# SparkFun_ESP8266_Thing_dimensions_added.net
KiCad netlist of a schematic drawn in EAGLE
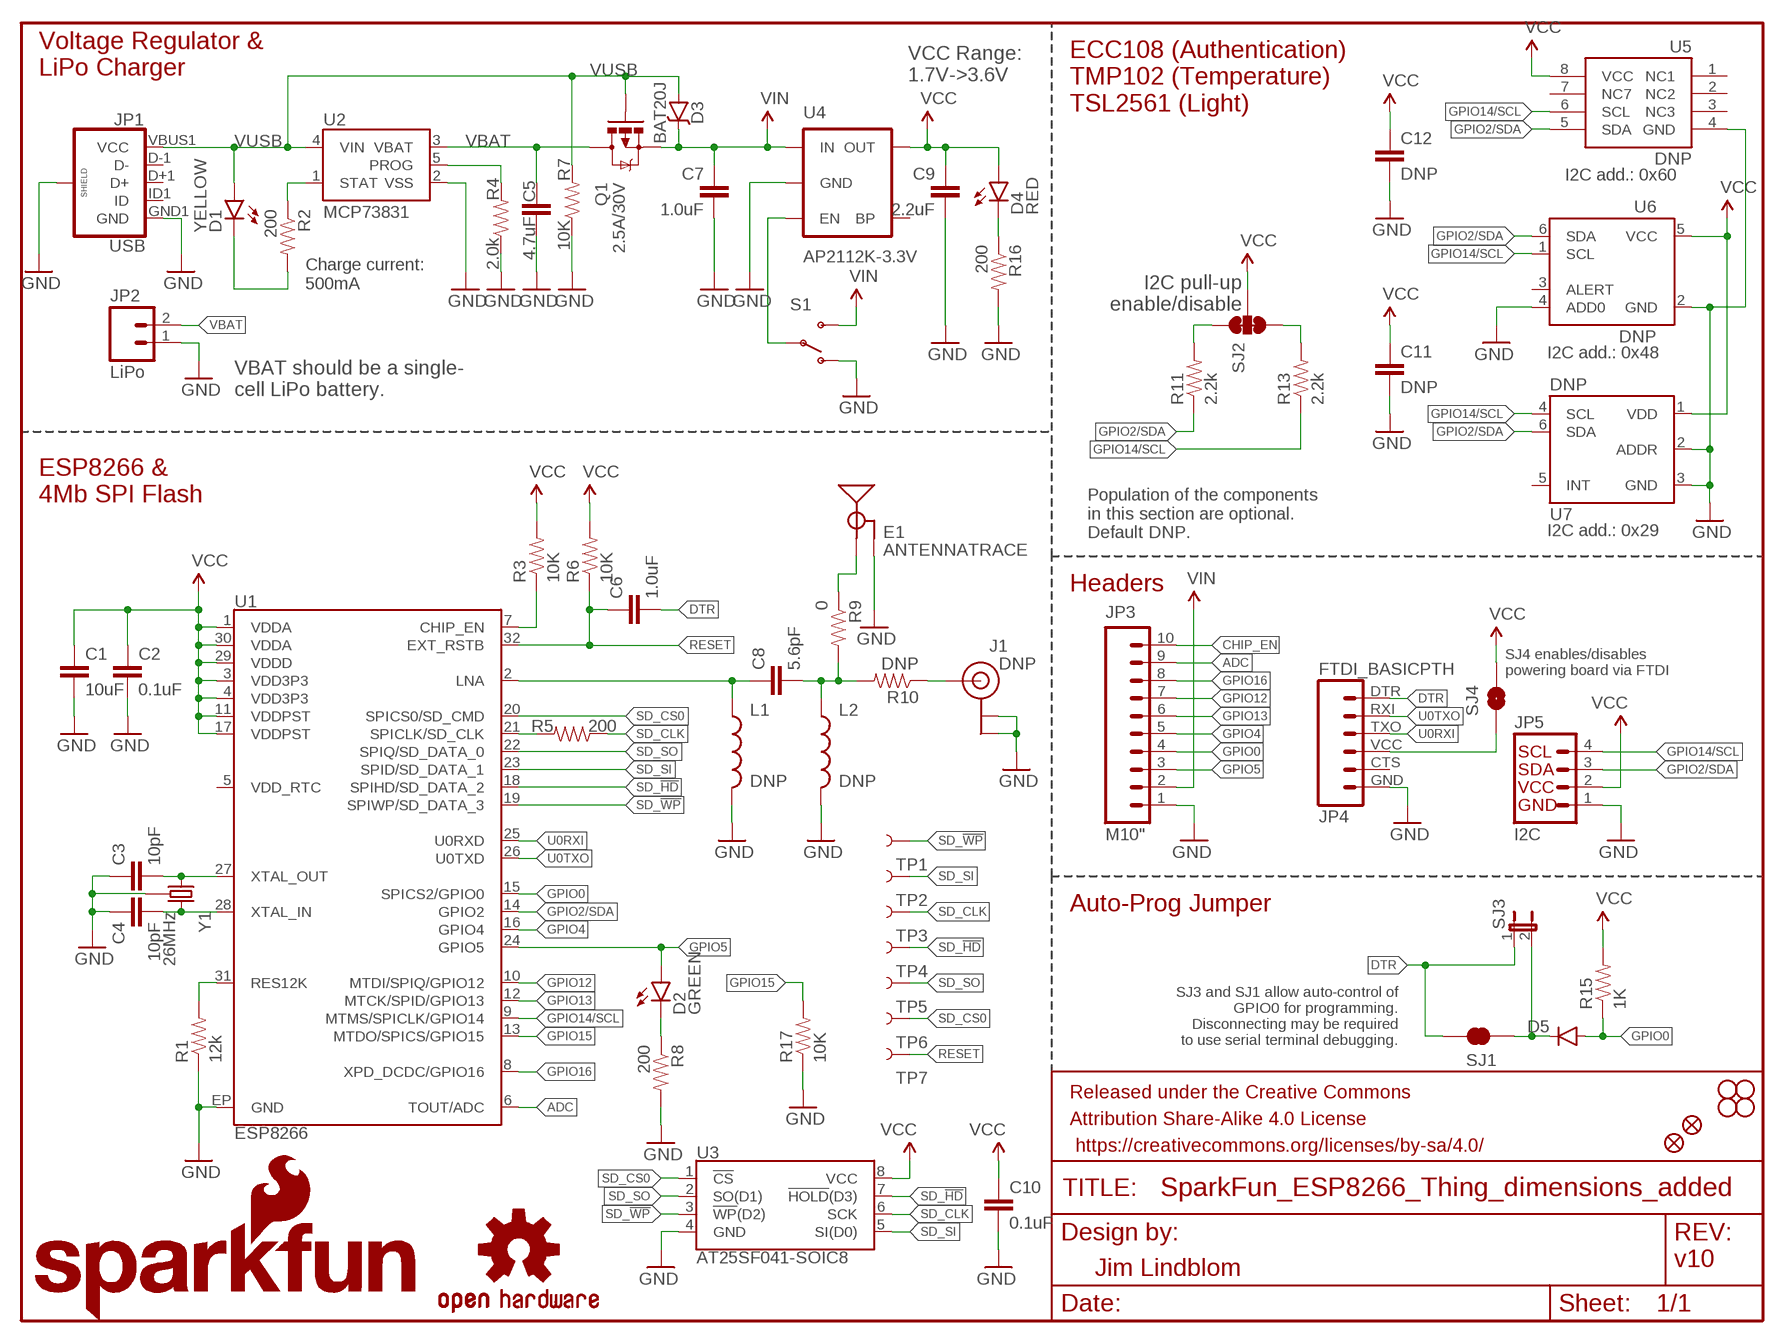
[diagram p0: schematic, sheet 1]

(export (version "E")
  (design (tool "Eeschema 10.0.6"))
  (components
    (comp (ref "C1")
      (value "10uF")
      (footprint "eagle-import:0603-CAP")
      (libsource (lib "eagle-import") (part "10UF-6.3V-20%(0603)"))
    )
    (comp (ref "C2")
      (value "0.1uF")
      (footprint "eagle-import:0603-CAP")
      (libsource (lib "eagle-import") (part "0.1UF-25V(+80/-20%)(0603)"))
    )
    (comp (ref "C3")
      (value "10pF")
      (footprint "eagle-import:0603-CAP")
      (libsource (lib "eagle-import") (part "10PF-50V-5%(0603)"))
    )
    (comp (ref "C4")
      (value "10pF")
      (footprint "eagle-import:0603-CAP")
      (libsource (lib "eagle-import") (part "10PF-50V-5%(0603)"))
    )
    (comp (ref "C5")
      (value "4.7uF")
      (footprint "eagle-import:0603-CAP")
      (libsource (lib "eagle-import") (part "4.7UF-6.3V-10%(0603)0603"))
    )
    (comp (ref "C6")
      (value "1.0uF")
      (footprint "eagle-import:0603-CAP")
      (libsource (lib "eagle-import") (part "1.0UF-16V-10%(0603)"))
    )
    (comp (ref "C7")
      (value "1.0uF")
      (footprint "eagle-import:0805")
      (libsource (lib "eagle-import") (part "1.0UF-25V-+80/-20(0805)"))
    )
    (comp (ref "C8")
      (value "5.6pF")
      (footprint "eagle-import:0603-CAP")
      (libsource (lib "eagle-import") (part "CAP0603-CAP"))
    )
    (comp (ref "C9")
      (value "2.2uF")
      (footprint "eagle-import:0603-CAP")
      (libsource (lib "eagle-import") (part "2.2UF-10V-20%(0603)"))
    )
    (comp (ref "C10")
      (value "0.1uF")
      (footprint "eagle-import:0603-CAP")
      (libsource (lib "eagle-import") (part "0.1UF-25V(+80/-20%)(0603)"))
    )
    (comp (ref "C11")
      (value "DNP")
      (footprint "eagle-import:0603-CAP")
      (libsource (lib "eagle-import") (part "0.1UF-25V(+80/-20%)(0603)"))
    )
    (comp (ref "C12")
      (value "DNP")
      (footprint "eagle-import:0603-CAP")
      (libsource (lib "eagle-import") (part "0.1UF-25V(+80/-20%)(0603)"))
    )
    (comp (ref "D1")
      (value "YELLOW")
      (footprint "eagle-import:LED-0603")
      (libsource (lib "eagle-import") (part "LED-YELLOW0603"))
    )
    (comp (ref "D2")
      (value "GREEN")
      (footprint "eagle-import:LED-0603")
      (libsource (lib "eagle-import") (part "LED-GREEN0603"))
    )
    (comp (ref "D3")
      (value "BAT20J")
      (footprint "eagle-import:SOD-323")
      (libsource (lib "eagle-import") (part "DIODE-SCHOTTKY-BAT20J"))
    )
    (comp (ref "D4")
      (value "RED")
      (footprint "eagle-import:LED-0603")
      (libsource (lib "eagle-import") (part "LED-RED0603"))
    )
    (comp (ref "D5")
      (value "DIODEBAS16")
      (footprint "eagle-import:SOD-323")
      (libsource (lib "eagle-import") (part "DIODEBAS16"))
    )
    (comp (ref "E1")
      (value "ANTENNATRACE")
      (footprint "eagle-import:TRACE_ANTENNA_2.4GHZ_25.7MM")
      (libsource (lib "eagle-import") (part "ANTENNATRACE"))
    )
    (comp (ref "FID1")
      (value "FIDUCIAL1X2")
      (footprint "eagle-import:FIDUCIAL-1X2")
      (libsource (lib "eagle-import") (part "FIDUCIAL1X2"))
    )
    (comp (ref "FID2")
      (value "FIDUCIAL1X2")
      (footprint "eagle-import:FIDUCIAL-1X2")
      (libsource (lib "eagle-import") (part "FIDUCIAL1X2"))
    )
    (comp (ref "FRAME1")
      (value "FRAME-LETTER")
      (footprint "eagle-import:CREATIVE_COMMONS")
      (libsource (lib "eagle-import") (part "FRAME-LETTER"))
    )
    (comp (ref "J1")
      (value "DNP")
      (footprint "eagle-import:U.FL")
      (libsource (lib "eagle-import") (part "U.FL"))
    )
    (comp (ref "JP1")
      (value "USB")
      (footprint "eagle-import:USB-B-MICRO-SMD_V03")
      (libsource (lib "eagle-import") (part "USB_MICROB_PLUGCONN-11752"))
    )
    (comp (ref "JP2")
      (value "LiPo")
      (footprint "eagle-import:JST-2-PTH")
      (libsource (lib "eagle-import") (part "M02JST-PTH-2"))
    )
    (comp (ref "JP3")
      (value "M10\"")
      (footprint "eagle-import:1X10")
      (libsource (lib "eagle-import") (part "M10{dblquote}"))
    )
    (comp (ref "JP4")
      (value "FTDI_BASICPTH")
      (footprint "eagle-import:FTDI_BASIC")
      (libsource (lib "eagle-import") (part "FTDI_BASICPTH"))
    )
    (comp (ref "JP5")
      (value "I2C")
      (footprint "eagle-import:1X04")
      (libsource (lib "eagle-import") (part "I2C_STANDARD"))
    )
    (comp (ref "L1")
      (value "DNP")
      (footprint "eagle-import:0603")
      (libsource (lib "eagle-import") (part "INDUCTOR0603"))
    )
    (comp (ref "L2")
      (value "DNP")
      (footprint "eagle-import:0603")
      (libsource (lib "eagle-import") (part "INDUCTOR0603"))
    )
    (comp (ref "LOGO1")
      (value "SFE_LOGO_NAME.2_INCH")
      (footprint "eagle-import:SFE_LOGO_NAME_.2")
      (libsource (lib "eagle-import") (part "SFE_LOGO_NAME.2_INCH"))
    )
    (comp (ref "LOGO3")
      (value "SFE_LOGO_FLAME.1_INCH")
      (footprint "eagle-import:SFE_LOGO_FLAME_.1")
      (libsource (lib "eagle-import") (part "SFE_LOGO_FLAME.1_INCH"))
    )
    (comp (ref "LOGO4")
      (value "OSHW-LOGOS")
      (footprint "eagle-import:OSHW-LOGO-S")
      (libsource (lib "eagle-import") (part "OSHW-LOGOS"))
    )
    (comp (ref "Q1")
      (value "2.5A/30V")
      (footprint "eagle-import:SOT23-3")
      (libsource (lib "eagle-import") (part "MOSFET-PCHANNELDMG2307L"))
    )
    (comp (ref "R1")
      (value "12k")
      (footprint "eagle-import:0603-RES")
      (libsource (lib "eagle-import") (part "12KOHM-1/10W-1%(0603)"))
    )
    (comp (ref "R2")
      (value "200")
      (footprint "eagle-import:0603-RES")
      (libsource (lib "eagle-import") (part "200OHM1/10W1%(0603)"))
    )
    (comp (ref "R3")
      (value "10K")
      (footprint "eagle-import:0603-RES")
      (libsource (lib "eagle-import") (part "10KOHM1/10W1%(0603)0603"))
    )
    (comp (ref "R4")
      (value "2.0k")
      (footprint "eagle-import:0603-RES")
      (libsource (lib "eagle-import") (part "2.0KOHM1/10W5%(0603)"))
    )
    (comp (ref "R5")
      (value "200")
      (footprint "eagle-import:0603-RES")
      (libsource (lib "eagle-import") (part "200OHM1/10W1%(0603)"))
    )
    (comp (ref "R6")
      (value "10K")
      (footprint "eagle-import:0603-RES")
      (libsource (lib "eagle-import") (part "10KOHM1/10W1%(0603)0603"))
    )
    (comp (ref "R7")
      (value "10K")
      (footprint "eagle-import:0603-RES")
      (libsource (lib "eagle-import") (part "10KOHM1/10W1%(0603)0603"))
    )
    (comp (ref "R8")
      (value "200")
      (footprint "eagle-import:0603-RES")
      (libsource (lib "eagle-import") (part "200OHM1/10W1%(0603)"))
    )
    (comp (ref "R9")
      (value "0")
      (footprint "eagle-import:0603")
      (libsource (lib "eagle-import") (part "0OHM1/10W5%(0603)"))
    )
    (comp (ref "R10")
      (value "DNP")
      (footprint "eagle-import:0603-RES")
      (libsource (lib "eagle-import") (part "RESISTOR0603-RES"))
    )
    (comp (ref "R11")
      (value "2.2k")
      (footprint "eagle-import:0603-RES")
      (libsource (lib "eagle-import") (part "2.2KOHM1/10W1%(0603)"))
    )
    (comp (ref "R13")
      (value "2.2k")
      (footprint "eagle-import:0603-RES")
      (libsource (lib "eagle-import") (part "2.2KOHM1/10W1%(0603)"))
    )
    (comp (ref "R15")
      (value "1K")
      (footprint "eagle-import:0603-RES")
      (libsource (lib "eagle-import") (part "1KOHM1/10W1%(0603)"))
    )
    (comp (ref "R16")
      (value "200")
      (footprint "eagle-import:0603-RES")
      (libsource (lib "eagle-import") (part "200OHM1/10W1%(0603)"))
    )
    (comp (ref "R17")
      (value "10K")
      (footprint "eagle-import:0603-RES")
      (libsource (lib "eagle-import") (part "10KOHM1/10W1%(0603)0603"))
    )
    (comp (ref "S1")
      (value "SWITCH-SPDT-SMD-A")
      (footprint "eagle-import:SWITCH-SPST-SMD-A")
      (libsource (lib "eagle-import") (part "SWITCH-SPDT-SMD-A"))
    )
    (comp (ref "SJ1")
      (value "JUMPER-PAD-2-NC_BY_TRACE")
      (footprint "eagle-import:PAD-JUMPER-2-NC_BY_TRACE_YES_SILK")
      (libsource (lib "eagle-import") (part "JUMPER-PAD-2-NC_BY_TRACE"))
    )
    (comp (ref "SJ2")
      (value "JUMPER-PAD-3-NC_BY_TRACE")
      (footprint "eagle-import:PAD-JUMPER-3-3OF3_NC_BY_TRACE_YES_SILK_FULL_BOX")
      (libsource (lib "eagle-import") (part "JUMPER-PAD-3-NC_BY_TRACE"))
    )
    (comp (ref "SJ3")
      (value "JUMPER-PTH-2-NC")
      (footprint "eagle-import:PTH-JUMPER-NC_BOTTOM_NO_SILK")
      (libsource (lib "eagle-import") (part "JUMPER-PTH-2-NC"))
    )
    (comp (ref "SJ4")
      (value "JUMPER-PAD-2-NOYES_SILK")
      (footprint "eagle-import:PAD-JUMPER-2-NO_YES_SILK")
      (libsource (lib "eagle-import") (part "JUMPER-PAD-2-NOYES_SILK"))
    )
    (comp (ref "STANDOFF1")
      (value "STAND-OFF")
      (footprint "eagle-import:STAND-OFF")
      (libsource (lib "eagle-import") (part "STAND-OFF"))
    )
    (comp (ref "STANDOFF2")
      (value "STAND-OFF")
      (footprint "eagle-import:STAND-OFF")
      (libsource (lib "eagle-import") (part "STAND-OFF"))
    )
    (comp (ref "STANDOFF3")
      (value "STAND-OFF")
      (footprint "eagle-import:STAND-OFF")
      (libsource (lib "eagle-import") (part "STAND-OFF"))
    )
    (comp (ref "STANDOFF4")
      (value "STAND-OFF")
      (footprint "eagle-import:STAND-OFF")
      (libsource (lib "eagle-import") (part "STAND-OFF"))
    )
    (comp (ref "TP1")
      (value "TEST-POINT3X5")
      (footprint "eagle-import:PAD.03X.05")
      (libsource (lib "eagle-import") (part "TEST-POINT3X5"))
    )
    (comp (ref "TP2")
      (value "TEST-POINT3X5")
      (footprint "eagle-import:PAD.03X.05")
      (libsource (lib "eagle-import") (part "TEST-POINT3X5"))
    )
    (comp (ref "TP3")
      (value "TEST-POINT3X5")
      (footprint "eagle-import:PAD.03X.05")
      (libsource (lib "eagle-import") (part "TEST-POINT3X5"))
    )
    (comp (ref "TP4")
      (value "TEST-POINT3X5")
      (footprint "eagle-import:PAD.03X.05")
      (libsource (lib "eagle-import") (part "TEST-POINT3X5"))
    )
    (comp (ref "TP5")
      (value "TEST-POINT3X5")
      (footprint "eagle-import:PAD.03X.05")
      (libsource (lib "eagle-import") (part "TEST-POINT3X5"))
    )
    (comp (ref "TP6")
      (value "TEST-POINT3X5")
      (footprint "eagle-import:PAD.03X.05")
      (libsource (lib "eagle-import") (part "TEST-POINT3X5"))
    )
    (comp (ref "TP7")
      (value "TEST-POINT3X5")
      (footprint "eagle-import:PAD.03X.05")
      (libsource (lib "eagle-import") (part "TEST-POINT3X5"))
    )
    (comp (ref "U1")
      (value "ESP8266")
      (footprint "eagle-import:QFN32")
      (libsource (lib "eagle-import") (part "ESP8266"))
    )
    (comp (ref "U2")
      (value "MCP73831")
      (footprint "eagle-import:SOT23-5")
      (libsource (lib "eagle-import") (part "MCP73831"))
    )
    (comp (ref "U3")
      (value "AT25SF041-SOIC8")
      (footprint "eagle-import:SO08")
      (libsource (lib "eagle-import") (part "AT25SF041-SOIC8"))
    )
    (comp (ref "U4")
      (value "AP2112K-3.3V")
      (footprint "eagle-import:SOT23-5")
      (libsource (lib "eagle-import") (part "V_REG_LDOSMD"))
    )
    (comp (ref "U5")
      (value "DNP")
      (footprint "eagle-import:UDFN8")
      (libsource (lib "eagle-import") (part "ATECC108-MAHDA"))
    )
    (comp (ref "U6")
      (value "DNP")
      (footprint "eagle-import:SOT563-2")
      (libsource (lib "eagle-import") (part "TMP1021{colon}1"))
    )
    (comp (ref "U7")
      (value "DNP")
      (footprint "eagle-import:FN-6")
      (libsource (lib "eagle-import") (part "TSL2561FN"))
    )
    (comp (ref "Y1")
      (value "26MHz")
      (footprint "eagle-import:CRYSTAL-SMD-3.2X2.5")
      (libsource (lib "eagle-import") (part "CRYSTAL-GROUNDED3.2X2.5"))
    )
  )
  (nets
    (net (code "1") (name "/SD_~{HD}") (class "Default")
      (node (ref "TP4") (pin "P$1") (pinfunction "1_P$1") (pintype "bidirectional"))
      (node (ref "U1") (pin "18") (pinfunction "SPIHD/SD_DATA_2_18") (pintype "bidirectional"))
      (node (ref "U3") (pin "7") (pinfunction "~{HOLD}(D3)_7") (pintype "bidirectional"))
    )
    (net (code "2") (name "/SD_~{WP}") (class "Default")
      (node (ref "TP1") (pin "P$1") (pinfunction "1_P$1") (pintype "bidirectional"))
      (node (ref "U1") (pin "19") (pinfunction "SPIWP/SD_DATA_3_19") (pintype "bidirectional"))
      (node (ref "U3") (pin "3") (pinfunction "~{WP}(D2)_3") (pintype "bidirectional"))
    )
    (net (code "3") (name "/VUSB") (class "Default")
      (node (ref "D1") (pin "A") (pinfunction "A_A") (pintype "passive"))
      (node (ref "D3") (pin "A") (pinfunction "A_A") (pintype "passive"))
      (node (ref "JP1") (pin "VBUS1") (pinfunction "VCC_VBUS1") (pintype "bidirectional"))
      (node (ref "Q1") (pin "1") (pinfunction "G_1") (pintype "passive"))
      (node (ref "R7") (pin "2") (pinfunction "2_2") (pintype "passive"))
      (node (ref "U2") (pin "4") (pinfunction "VIN_4") (pintype "power_in"))
    )
    (net (code "4") (name "ADC") (class "Default")
      (node (ref "JP3") (pin "9") (pinfunction "9_9") (pintype "passive"))
      (node (ref "U1") (pin "6") (pinfunction "TOUT/ADC_6") (pintype "bidirectional"))
    )
    (net (code "5") (name "CHIP_EN") (class "Default")
      (node (ref "JP3") (pin "10") (pinfunction "10_10") (pintype "passive"))
      (node (ref "R3") (pin "1") (pinfunction "1_1") (pintype "passive"))
      (node (ref "U1") (pin "7") (pinfunction "CHIP_EN_7") (pintype "bidirectional"))
    )
    (net (code "6") (name "DTR") (class "Default")
      (node (ref "C6") (pin "2") (pinfunction "2_2") (pintype "passive"))
      (node (ref "JP4") (pin "DTR") (pinfunction "1_DTR") (pintype "passive"))
      (node (ref "SJ1") (pin "2") (pinfunction "2_2") (pintype "passive"))
      (node (ref "SJ3") (pin "1") (pinfunction "1_1") (pintype "passive"))
    )
    (net (code "7") (name "GND") (class "Default")
      (node (ref "C1") (pin "2") (pinfunction "2_2") (pintype "passive"))
      (node (ref "C10") (pin "2") (pinfunction "2_2") (pintype "passive"))
      (node (ref "C11") (pin "2") (pinfunction "2_2") (pintype "passive"))
      (node (ref "C12") (pin "2") (pinfunction "2_2") (pintype "passive"))
      (node (ref "C2") (pin "2") (pinfunction "2_2") (pintype "passive"))
      (node (ref "C3") (pin "1") (pinfunction "1_1") (pintype "passive"))
      (node (ref "C4") (pin "1") (pinfunction "1_1") (pintype "passive"))
      (node (ref "C5") (pin "2") (pinfunction "2_2") (pintype "passive"))
      (node (ref "C7") (pin "2") (pinfunction "2_2") (pintype "passive"))
      (node (ref "C9") (pin "2") (pinfunction "2_2") (pintype "passive"))
      (node (ref "E1") (pin "GND") (pinfunction "GND_GND") (pintype "bidirectional"))
      (node (ref "E1") (pin "GND2") (pinfunction "GND_GND2") (pintype "bidirectional"))
      (node (ref "J1") (pin "P$1") (pinfunction "GND_P$1") (pintype "bidirectional"))
      (node (ref "J1") (pin "P$2") (pinfunction "GND_P$2") (pintype "bidirectional"))
      (node (ref "JP1") (pin "GND1") (pinfunction "GND_GND1") (pintype "bidirectional"))
      (node (ref "JP1") (pin "SHIELD1") (pinfunction "SHIELD_SHIELD1") (pintype "bidirectional"))
      (node (ref "JP1") (pin "SHIELD2") (pinfunction "SHIELD_SHIELD2") (pintype "bidirectional"))
      (node (ref "JP1") (pin "SHIELD3") (pinfunction "SHIELD_SHIELD3") (pintype "bidirectional"))
      (node (ref "JP2") (pin "1") (pinfunction "1_1") (pintype "passive"))
      (node (ref "JP3") (pin "1") (pinfunction "1_1") (pintype "passive"))
      (node (ref "JP4") (pin "GND") (pinfunction "6_GND") (pintype "passive"))
      (node (ref "JP5") (pin "1") (pinfunction "1_1") (pintype "passive"))
      (node (ref "L1") (pin "2") (pinfunction "2_2") (pintype "passive"))
      (node (ref "L2") (pin "2") (pinfunction "2_2") (pintype "passive"))
      (node (ref "R1") (pin "1") (pinfunction "1_1") (pintype "passive"))
      (node (ref "R16") (pin "2") (pinfunction "2_2") (pintype "passive"))
      (node (ref "R17") (pin "1") (pinfunction "1_1") (pintype "passive"))
      (node (ref "R4") (pin "1") (pinfunction "1_1") (pintype "passive"))
      (node (ref "R7") (pin "1") (pinfunction "1_1") (pintype "passive"))
      (node (ref "R8") (pin "2") (pinfunction "2_2") (pintype "passive"))
      (node (ref "S1") (pin "1") (pinfunction "O_1") (pintype "passive"))
      (node (ref "U1") (pin "EP") (pinfunction "GND_EP") (pintype "bidirectional"))
      (node (ref "U2") (pin "2") (pinfunction "VSS_2") (pintype "power_in"))
      (node (ref "U3") (pin "4") (pinfunction "GND_4") (pintype "bidirectional"))
      (node (ref "U4") (pin "2") (pinfunction "GND_2") (pintype "input"))
      (node (ref "U5") (pin "4") (pinfunction "GND_4") (pintype "power_in"))
      (node (ref "U6") (pin "2") (pinfunction "GND_2") (pintype "bidirectional"))
      (node (ref "U6") (pin "4") (pinfunction "ADD0_4") (pintype "bidirectional"))
      (node (ref "U7") (pin "2") (pinfunction "ADDR_2") (pintype "input"))
      (node (ref "U7") (pin "3") (pinfunction "GND_3") (pintype "power_in"))
      (node (ref "Y1") (pin "2") (pinfunction "GND_2") (pintype "passive"))
      (node (ref "Y1") (pin "4") (pinfunction "GND_4") (pintype "passive"))
    )
    (net (code "8") (name "GPIO0") (class "Default")
      (node (ref "D5") (pin "A") (pinfunction "A_A") (pintype "passive"))
      (node (ref "JP3") (pin "4") (pinfunction "4_4") (pintype "passive"))
      (node (ref "R15") (pin "1") (pinfunction "1_1") (pintype "passive"))
      (node (ref "U1") (pin "15") (pinfunction "SPICS2/GPIO0_15") (pintype "bidirectional"))
    )
    (net (code "9") (name "GPIO2{slash}SDA") (class "Default")
      (node (ref "JP5") (pin "3") (pinfunction "3_3") (pintype "passive"))
      (node (ref "R11") (pin "1") (pinfunction "1_1") (pintype "passive"))
      (node (ref "U1") (pin "14") (pinfunction "GPIO2_14") (pintype "bidirectional"))
      (node (ref "U5") (pin "5") (pinfunction "SDA_5") (pintype "bidirectional"))
      (node (ref "U6") (pin "6") (pinfunction "SDA_6") (pintype "bidirectional"))
      (node (ref "U7") (pin "6") (pinfunction "SDA_6") (pintype "bidirectional"))
    )
    (net (code "10") (name "GPIO4") (class "Default")
      (node (ref "JP3") (pin "5") (pinfunction "5_5") (pintype "passive"))
      (node (ref "U1") (pin "16") (pinfunction "GPIO4_16") (pintype "bidirectional"))
    )
    (net (code "11") (name "GPIO5") (class "Default")
      (node (ref "D2") (pin "A") (pinfunction "A_A") (pintype "passive"))
      (node (ref "JP3") (pin "3") (pinfunction "3_3") (pintype "passive"))
      (node (ref "U1") (pin "24") (pinfunction "GPIO5_24") (pintype "bidirectional"))
    )
    (net (code "12") (name "GPIO12") (class "Default")
      (node (ref "JP3") (pin "7") (pinfunction "7_7") (pintype "passive"))
      (node (ref "U1") (pin "10") (pinfunction "MTDI/SPIQ/GPIO12_10") (pintype "bidirectional"))
    )
    (net (code "13") (name "GPIO13") (class "Default")
      (node (ref "JP3") (pin "6") (pinfunction "6_6") (pintype "passive"))
      (node (ref "U1") (pin "12") (pinfunction "MTCK/SPID/GPIO13_12") (pintype "bidirectional"))
    )
    (net (code "14") (name "GPIO14{slash}SCL") (class "Default")
      (node (ref "JP5") (pin "4") (pinfunction "4_4") (pintype "passive"))
      (node (ref "R13") (pin "1") (pinfunction "1_1") (pintype "passive"))
      (node (ref "U1") (pin "9") (pinfunction "MTMS/SPICLK/GPIO14_9") (pintype "bidirectional"))
      (node (ref "U5") (pin "6") (pinfunction "SCL_6") (pintype "bidirectional"))
      (node (ref "U6") (pin "1") (pinfunction "SCL_1") (pintype "bidirectional"))
      (node (ref "U7") (pin "4") (pinfunction "SCL_4") (pintype "input"))
    )
    (net (code "15") (name "GPIO15") (class "Default")
      (node (ref "R17") (pin "2") (pinfunction "2_2") (pintype "passive"))
      (node (ref "U1") (pin "13") (pinfunction "MTDO/SPICS/GPIO15_13") (pintype "bidirectional"))
    )
    (net (code "16") (name "GPIO16") (class "Default")
      (node (ref "JP3") (pin "8") (pinfunction "8_8") (pintype "passive"))
      (node (ref "U1") (pin "8") (pinfunction "XPD_DCDC/GPIO16_8") (pintype "bidirectional"))
    )
    (net (code "17") (name "Net-(C8-Pad2)") (class "Default")
      (node (ref "C8") (pin "2") (pinfunction "2_2") (pintype "passive"))
      (node (ref "L2") (pin "1") (pinfunction "1_1") (pintype "passive"))
      (node (ref "R10") (pin "2") (pinfunction "2_2") (pintype "passive"))
      (node (ref "R9") (pin "2") (pinfunction "2_2") (pintype "passive"))
    )
    (net (code "18") (name "Net-(D1-PadC)") (class "Default")
      (node (ref "D1") (pin "C") (pinfunction "C_C") (pintype "passive"))
      (node (ref "R2") (pin "2") (pinfunction "2_2") (pintype "passive"))
    )
    (net (code "19") (name "Net-(D2-PadC)") (class "Default")
      (node (ref "D2") (pin "C") (pinfunction "C_C") (pintype "passive"))
      (node (ref "R8") (pin "1") (pinfunction "1_1") (pintype "passive"))
    )
    (net (code "20") (name "Net-(D4-PadC)") (class "Default")
      (node (ref "D4") (pin "C") (pinfunction "C_C") (pintype "passive"))
      (node (ref "R16") (pin "1") (pinfunction "1_1") (pintype "passive"))
    )
    (net (code "21") (name "Net-(D5-PadC)") (class "Default")
      (node (ref "D5") (pin "C") (pinfunction "C_C") (pintype "passive"))
      (node (ref "SJ1") (pin "1") (pinfunction "1_1") (pintype "passive"))
      (node (ref "SJ3") (pin "2") (pinfunction "2_2") (pintype "passive"))
    )
    (net (code "22") (name "Net-(E1-SIGNAL)") (class "Default")
      (node (ref "E1") (pin "ANT") (pinfunction "SIGNAL_ANT") (pintype "bidirectional"))
      (node (ref "R9") (pin "1") (pinfunction "1_1") (pintype "passive"))
    )
    (net (code "23") (name "Net-(J1-SIGNAL)") (class "Default")
      (node (ref "J1") (pin "P$3") (pinfunction "SIGNAL_P$3") (pintype "bidirectional"))
      (node (ref "R10") (pin "1") (pinfunction "1_1") (pintype "passive"))
    )
    (net (code "24") (name "Net-(JP4-4)") (class "Default")
      (node (ref "JP4") (pin "VCC") (pinfunction "4_VCC") (pintype "passive"))
      (node (ref "SJ4") (pin "1") (pinfunction "1_1") (pintype "passive"))
    )
    (net (code "25") (name "Net-(R11-Pad2)") (class "Default")
      (node (ref "R11") (pin "2") (pinfunction "2_2") (pintype "passive"))
      (node (ref "SJ2") (pin "1") (pinfunction "1_1") (pintype "passive"))
    )
    (net (code "26") (name "Net-(R13-Pad2)") (class "Default")
      (node (ref "R13") (pin "2") (pinfunction "2_2") (pintype "passive"))
      (node (ref "SJ2") (pin "3") (pinfunction "3_3") (pintype "passive"))
    )
    (net (code "27") (name "Net-(S1-P)") (class "Default")
      (node (ref "S1") (pin "2") (pinfunction "P_2") (pintype "passive"))
      (node (ref "U4") (pin "3") (pinfunction "EN_3") (pintype "input"))
    )
    (net (code "28") (name "Net-(U1-LNA)") (class "Default")
      (node (ref "C8") (pin "1") (pinfunction "1_1") (pintype "passive"))
      (node (ref "L1") (pin "1") (pinfunction "1_1") (pintype "passive"))
      (node (ref "U1") (pin "2") (pinfunction "LNA_2") (pintype "bidirectional"))
    )
    (net (code "29") (name "Net-(U1-RES12K)") (class "Default")
      (node (ref "R1") (pin "2") (pinfunction "2_2") (pintype "passive"))
      (node (ref "U1") (pin "31") (pinfunction "RES12K_31") (pintype "bidirectional"))
    )
    (net (code "30") (name "Net-(U1-SPICLK{slash}SD_CLK)") (class "Default")
      (node (ref "R5") (pin "2") (pinfunction "2_2") (pintype "passive"))
      (node (ref "U1") (pin "21") (pinfunction "SPICLK/SD_CLK_21") (pintype "bidirectional"))
    )
    (net (code "31") (name "Net-(U1-XTAL_IN)") (class "Default")
      (node (ref "C4") (pin "2") (pinfunction "2_2") (pintype "passive"))
      (node (ref "U1") (pin "28") (pinfunction "XTAL_IN_28") (pintype "bidirectional"))
      (node (ref "Y1") (pin "3") (pinfunction "2_3") (pintype "passive"))
    )
    (net (code "32") (name "Net-(U1-XTAL_OUT)") (class "Default")
      (node (ref "C3") (pin "2") (pinfunction "2_2") (pintype "passive"))
      (node (ref "U1") (pin "27") (pinfunction "XTAL_OUT_27") (pintype "bidirectional"))
      (node (ref "Y1") (pin "1") (pinfunction "1_1") (pintype "passive"))
    )
    (net (code "33") (name "Net-(U2-PROG)") (class "Default")
      (node (ref "R4") (pin "2") (pinfunction "2_2") (pintype "passive"))
      (node (ref "U2") (pin "5") (pinfunction "PROG_5") (pintype "input"))
    )
    (net (code "34") (name "Net-(U2-STAT)") (class "Default")
      (node (ref "R2") (pin "1") (pinfunction "1_1") (pintype "passive"))
      (node (ref "U2") (pin "1") (pinfunction "STAT_1") (pintype "output"))
    )
    (net (code "35") (name "RESET") (class "Default")
      (node (ref "C6") (pin "1") (pinfunction "1_1") (pintype "passive"))
      (node (ref "R6") (pin "1") (pinfunction "1_1") (pintype "passive"))
      (node (ref "TP7") (pin "P$1") (pinfunction "1_P$1") (pintype "bidirectional"))
      (node (ref "U1") (pin "32") (pinfunction "EXT_RSTB_32") (pintype "bidirectional"))
    )
    (net (code "36") (name "SD_CLK") (class "Default")
      (node (ref "R5") (pin "1") (pinfunction "1_1") (pintype "passive"))
      (node (ref "TP3") (pin "P$1") (pinfunction "1_P$1") (pintype "bidirectional"))
      (node (ref "U3") (pin "6") (pinfunction "SCK_6") (pintype "bidirectional"))
    )
    (net (code "37") (name "SD_CS0") (class "Default")
      (node (ref "TP6") (pin "P$1") (pinfunction "1_P$1") (pintype "bidirectional"))
      (node (ref "U1") (pin "20") (pinfunction "SPICS0/SD_CMD_20") (pintype "bidirectional"))
      (node (ref "U3") (pin "1") (pinfunction "~{CS}_1") (pintype "bidirectional"))
    )
    (net (code "38") (name "SD_SI") (class "Default")
      (node (ref "TP2") (pin "P$1") (pinfunction "1_P$1") (pintype "bidirectional"))
      (node (ref "U1") (pin "23") (pinfunction "SPID/SD_DATA_1_23") (pintype "bidirectional"))
      (node (ref "U3") (pin "5") (pinfunction "SI(D0)_5") (pintype "bidirectional"))
    )
    (net (code "39") (name "SD_SO") (class "Default")
      (node (ref "TP5") (pin "P$1") (pinfunction "1_P$1") (pintype "bidirectional"))
      (node (ref "U1") (pin "22") (pinfunction "SPIQ/SD_DATA_0_22") (pintype "bidirectional"))
      (node (ref "U3") (pin "2") (pinfunction "SO(D1)_2") (pintype "bidirectional"))
    )
    (net (code "40") (name "U0RXI") (class "Default")
      (node (ref "JP4") (pin "TXO") (pinfunction "3_TXO") (pintype "passive"))
      (node (ref "U1") (pin "25") (pinfunction "U0RXD_25") (pintype "bidirectional"))
    )
    (net (code "41") (name "U0TXO") (class "Default")
      (node (ref "JP4") (pin "RXI") (pinfunction "2_RXI") (pintype "passive"))
      (node (ref "U1") (pin "26") (pinfunction "U0TXD_26") (pintype "bidirectional"))
    )
    (net (code "42") (name "VBAT") (class "Default")
      (node (ref "C5") (pin "1") (pinfunction "1_1") (pintype "passive"))
      (node (ref "JP2") (pin "2") (pinfunction "2_2") (pintype "passive"))
      (node (ref "Q1") (pin "3") (pinfunction "D_3") (pintype "passive"))
      (node (ref "U2") (pin "3") (pinfunction "VBAT_3") (pintype "power_in"))
    )
    (net (code "43") (name "VCC") (class "Default")
      (node (ref "C1") (pin "1") (pinfunction "1_1") (pintype "passive"))
      (node (ref "C10") (pin "1") (pinfunction "1_1") (pintype "passive"))
      (node (ref "C11") (pin "1") (pinfunction "1_1") (pintype "passive"))
      (node (ref "C12") (pin "1") (pinfunction "1_1") (pintype "passive"))
      (node (ref "C2") (pin "1") (pinfunction "1_1") (pintype "passive"))
      (node (ref "C9") (pin "1") (pinfunction "1_1") (pintype "passive"))
      (node (ref "D4") (pin "A") (pinfunction "A_A") (pintype "passive"))
      (node (ref "JP5") (pin "2") (pinfunction "2_2") (pintype "passive"))
      (node (ref "R15") (pin "2") (pinfunction "2_2") (pintype "passive"))
      (node (ref "R3") (pin "2") (pinfunction "2_2") (pintype "passive"))
      (node (ref "R6") (pin "2") (pinfunction "2_2") (pintype "passive"))
      (node (ref "SJ2") (pin "2") (pinfunction "2_2") (pintype "passive"))
      (node (ref "SJ4") (pin "2") (pinfunction "2_2") (pintype "passive"))
      (node (ref "U1") (pin "1") (pinfunction "VDDA_1") (pintype "bidirectional"))
      (node (ref "U1") (pin "11") (pinfunction "VDDPST_11") (pintype "bidirectional"))
      (node (ref "U1") (pin "17") (pinfunction "VDDPST_17") (pintype "bidirectional"))
      (node (ref "U1") (pin "29") (pinfunction "VDDD_29") (pintype "bidirectional"))
      (node (ref "U1") (pin "3") (pinfunction "VDD3P3_3") (pintype "bidirectional"))
      (node (ref "U1") (pin "30") (pinfunction "VDDA_30") (pintype "bidirectional"))
      (node (ref "U1") (pin "4") (pinfunction "VDD3P3_4") (pintype "bidirectional"))
      (node (ref "U3") (pin "8") (pinfunction "VCC_8") (pintype "bidirectional"))
      (node (ref "U4") (pin "5") (pinfunction "OUT_5") (pintype "passive"))
      (node (ref "U5") (pin "8") (pinfunction "VCC_8") (pintype "power_in"))
      (node (ref "U6") (pin "5") (pinfunction "VCC_5") (pintype "bidirectional"))
      (node (ref "U7") (pin "1") (pinfunction "VDD_1") (pintype "power_in"))
    )
    (net (code "44") (name "VIN") (class "Default")
      (node (ref "C7") (pin "1") (pinfunction "1_1") (pintype "passive"))
      (node (ref "D3") (pin "C") (pinfunction "C_C") (pintype "passive"))
      (node (ref "JP3") (pin "2") (pinfunction "2_2") (pintype "passive"))
      (node (ref "Q1") (pin "2") (pinfunction "S_2") (pintype "passive"))
      (node (ref "S1") (pin "3") (pinfunction "S_3") (pintype "passive"))
      (node (ref "U4") (pin "1") (pinfunction "IN_1") (pintype "input"))
    )
    (net (code "45") (name "unconnected-(JP1-D+-PadD+1)") (class "Default")
      (node (ref "JP1") (pin "D+1") (pinfunction "D+_D+1") (pintype "bidirectional"))
    )
    (net (code "46") (name "unconnected-(JP1-D--PadD-1)") (class "Default")
      (node (ref "JP1") (pin "D-1") (pinfunction "D-_D-1") (pintype "bidirectional"))
    )
    (net (code "47") (name "unconnected-(JP1-ID-PadID1)") (class "Default")
      (node (ref "JP1") (pin "ID1") (pinfunction "ID_ID1") (pintype "bidirectional"))
    )
    (net (code "48") (name "unconnected-(JP4-5-PadCTS)") (class "Default")
      (node (ref "JP4") (pin "CTS") (pinfunction "5_CTS") (pintype "passive"))
    )
    (net (code "49") (name "unconnected-(U1-VDD_RTC-Pad5)") (class "Default")
      (node (ref "U1") (pin "5") (pinfunction "VDD_RTC_5") (pintype "bidirectional"))
    )
    (net (code "50") (name "unconnected-(U4-BP-Pad4)") (class "Default")
      (node (ref "U4") (pin "4") (pinfunction "BP_4") (pintype "input"))
    )
    (net (code "51") (name "unconnected-(U5-NC1-Pad1)") (class "Default")
      (node (ref "U5") (pin "1") (pinfunction "NC1_1") (pintype "bidirectional"))
    )
    (net (code "52") (name "unconnected-(U5-NC2-Pad2)") (class "Default")
      (node (ref "U5") (pin "2") (pinfunction "NC2_2") (pintype "no_connect"))
    )
    (net (code "53") (name "unconnected-(U5-NC3-Pad3)") (class "Default")
      (node (ref "U5") (pin "3") (pinfunction "NC3_3") (pintype "no_connect"))
    )
    (net (code "54") (name "unconnected-(U5-NC7-Pad7)") (class "Default")
      (node (ref "U5") (pin "7") (pinfunction "NC7_7") (pintype "no_connect"))
    )
    (net (code "55") (name "unconnected-(U6-ALERT-Pad3)") (class "Default")
      (node (ref "U6") (pin "3") (pinfunction "ALERT_3") (pintype "bidirectional"))
    )
    (net (code "56") (name "unconnected-(U7-INT-Pad5)") (class "Default")
      (node (ref "U7") (pin "5") (pinfunction "INT_5") (pintype "output"))
    )
  )
)
